# QCopterRC_EXTERN_Sch.net
KiCad netlist of a schematic drawn in Altium Designer
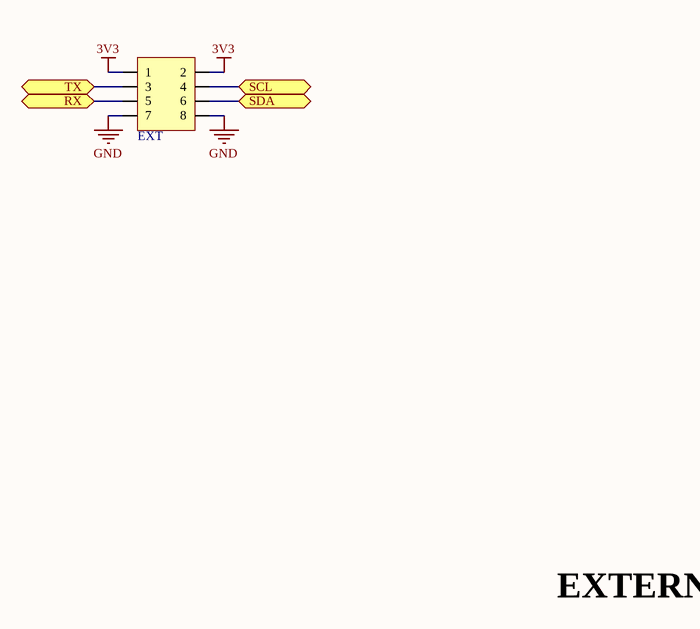
[diagram p0: QCopterRC_EXTERN_Sch.SchDoc]

(export (version "E")
  (design (tool "Eeschema 10.0.6"))
  (components
    (comp (ref "EXT")
      (value "HDR2X4_90_2.54")
      (footprint "PCB_Connector:HDR2X4_90_2.54")
      (description "Header")
      (libsource (lib "SCH_Connector") (part "HDR2X4_90_2.54"))
    )
  )
  (nets
    (net (code "2") (name "/RX") (class "Default")
      (node (ref "EXT") (pin "5") (pinfunction "5_5") (pintype "passive"))
    )
    (net (code "3") (name "/SCL") (class "Default")
      (node (ref "EXT") (pin "4") (pinfunction "4_4") (pintype "passive"))
    )
    (net (code "4") (name "/SDA") (class "Default")
      (node (ref "EXT") (pin "6") (pinfunction "6_6") (pintype "passive"))
    )
    (net (code "5") (name "/TX") (class "Default")
      (node (ref "EXT") (pin "3") (pinfunction "3_3") (pintype "passive"))
    )
    (net (code "6") (name "3V3") (class "Default")
      (node (ref "EXT") (pin "1") (pinfunction "1_1") (pintype "passive"))
      (node (ref "EXT") (pin "2") (pinfunction "2_2") (pintype "passive"))
    )
    (net (code "7") (name "GND") (class "Default")
      (node (ref "EXT") (pin "7") (pinfunction "7_7") (pintype "passive"))
      (node (ref "EXT") (pin "8") (pinfunction "8_8") (pintype "passive"))
    )
  )
)
